# 04_MR_WOLF.net
KiCad netlist of a schematic drawn in Altium Designer
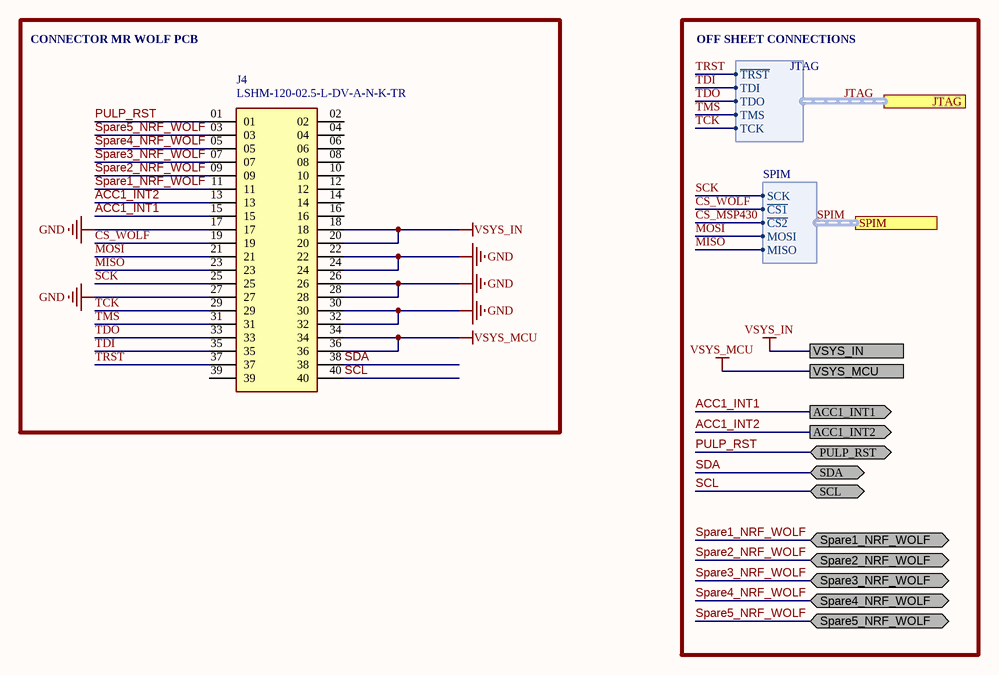
[diagram p0: 04_MR_WOLF.SchDoc]

(export (version "E")
  (design (tool "Eeschema 10.0.6"))
  (components
    (comp (ref "J4")
      (value "LSHM-120-02.5-L-DV-A-N-K-TR")
      (footprint "PcbLib1:SAMTEC_LSHM-120-XX.X-X-DV-A-N-XX")
      (description "Conn Socket and Terminal Strip HDR/SKT 40 POS 0.5mm Solder ST SMD T/R")
      (fields
        (field (name "MANUFACTURER") "Samtec")
        (field (name "MANUFACTURER PART NUMBER") "LSHM-120-02.5-L-DV-A-N-K-TR")
      )
      (libsource (lib "Schlib1") (part "LSHM-120-02.5-L-DV-A-N-K-TR"))
    )
  )
  (nets
    (net (code "3") (name "/ACC1_INT1") (class "Default")
      (node (ref "J4") (pin "15") (pinfunction "15_15") (pintype "passive"))
    )
    (net (code "4") (name "/ACC1_INT2") (class "Default")
      (node (ref "J4") (pin "13") (pinfunction "13_13") (pintype "passive"))
    )
    (net (code "6") (name "/CS_WOLF") (class "Default")
      (node (ref "J4") (pin "19") (pinfunction "19_19") (pintype "passive"))
    )
    (net (code "8") (name "/MISO") (class "Default")
      (node (ref "J4") (pin "23") (pinfunction "23_23") (pintype "passive"))
    )
    (net (code "9") (name "/MOSI") (class "Default")
      (node (ref "J4") (pin "21") (pinfunction "21_21") (pintype "passive"))
    )
    (net (code "10") (name "/PULP_RST") (class "Default")
      (node (ref "J4") (pin "01") (pinfunction "01_01") (pintype "passive"))
    )
    (net (code "11") (name "/SCK") (class "Default")
      (node (ref "J4") (pin "25") (pinfunction "25_25") (pintype "passive"))
    )
    (net (code "12") (name "/SCL") (class "Default")
      (node (ref "J4") (pin "40") (pinfunction "40_40") (pintype "passive"))
    )
    (net (code "13") (name "/SDA") (class "Default")
      (node (ref "J4") (pin "38") (pinfunction "38_38") (pintype "passive"))
    )
    (net (code "15") (name "/Spare1_NRF_WOLF") (class "Default")
      (node (ref "J4") (pin "11") (pinfunction "11_11") (pintype "passive"))
    )
    (net (code "16") (name "/Spare2_NRF_WOLF") (class "Default")
      (node (ref "J4") (pin "09") (pinfunction "09_09") (pintype "passive"))
    )
    (net (code "17") (name "/Spare3_NRF_WOLF") (class "Default")
      (node (ref "J4") (pin "07") (pinfunction "07_07") (pintype "passive"))
    )
    (net (code "18") (name "/Spare4_NRF_WOLF") (class "Default")
      (node (ref "J4") (pin "05") (pinfunction "05_05") (pintype "passive"))
    )
    (net (code "19") (name "/Spare5_NRF_WOLF") (class "Default")
      (node (ref "J4") (pin "03") (pinfunction "03_03") (pintype "passive"))
    )
    (net (code "20") (name "/TCK") (class "Default")
      (node (ref "J4") (pin "29") (pinfunction "29_29") (pintype "passive"))
    )
    (net (code "21") (name "/TDI") (class "Default")
      (node (ref "J4") (pin "35") (pinfunction "35_35") (pintype "passive"))
    )
    (net (code "22") (name "/TDO") (class "Default")
      (node (ref "J4") (pin "33") (pinfunction "33_33") (pintype "passive"))
    )
    (net (code "23") (name "/TMS") (class "Default")
      (node (ref "J4") (pin "31") (pinfunction "31_31") (pintype "passive"))
    )
    (net (code "24") (name "/TRST") (class "Default")
      (node (ref "J4") (pin "37") (pinfunction "37_37") (pintype "passive"))
    )
    (net (code "25") (name "GND") (class "Default")
      (node (ref "J4") (pin "17") (pinfunction "17_17") (pintype "passive"))
      (node (ref "J4") (pin "22") (pinfunction "22_22") (pintype "passive"))
      (node (ref "J4") (pin "24") (pinfunction "24_24") (pintype "passive"))
      (node (ref "J4") (pin "26") (pinfunction "26_26") (pintype "passive"))
      (node (ref "J4") (pin "27") (pinfunction "27_27") (pintype "passive"))
      (node (ref "J4") (pin "28") (pinfunction "28_28") (pintype "passive"))
      (node (ref "J4") (pin "30") (pinfunction "30_30") (pintype "passive"))
      (node (ref "J4") (pin "32") (pinfunction "32_32") (pintype "passive"))
    )
    (net (code "26") (name "VSYS_IN") (class "Default")
      (node (ref "J4") (pin "18") (pinfunction "18_18") (pintype "passive"))
      (node (ref "J4") (pin "20") (pinfunction "20_20") (pintype "passive"))
    )
    (net (code "27") (name "VSYS_MCU") (class "Default")
      (node (ref "J4") (pin "34") (pinfunction "34_34") (pintype "passive"))
      (node (ref "J4") (pin "36") (pinfunction "36_36") (pintype "passive"))
    )
    (net (code "28") (name "unconnected-(J4-Pad02)") (class "Default")
      (node (ref "J4") (pin "02") (pinfunction "02_02") (pintype "passive"))
    )
    (net (code "29") (name "unconnected-(J4-Pad04)") (class "Default")
      (node (ref "J4") (pin "04") (pinfunction "04_04") (pintype "passive"))
    )
    (net (code "30") (name "unconnected-(J4-Pad06)") (class "Default")
      (node (ref "J4") (pin "06") (pinfunction "06_06") (pintype "passive"))
    )
    (net (code "31") (name "unconnected-(J4-Pad08)") (class "Default")
      (node (ref "J4") (pin "08") (pinfunction "08_08") (pintype "passive"))
    )
    (net (code "32") (name "unconnected-(J4-Pad10)") (class "Default")
      (node (ref "J4") (pin "10") (pinfunction "10_10") (pintype "passive"))
    )
    (net (code "33") (name "unconnected-(J4-Pad12)") (class "Default")
      (node (ref "J4") (pin "12") (pinfunction "12_12") (pintype "passive"))
    )
    (net (code "34") (name "unconnected-(J4-Pad14)") (class "Default")
      (node (ref "J4") (pin "14") (pinfunction "14_14") (pintype "passive"))
    )
    (net (code "35") (name "unconnected-(J4-Pad16)") (class "Default")
      (node (ref "J4") (pin "16") (pinfunction "16_16") (pintype "passive"))
    )
    (net (code "36") (name "unconnected-(J4-Pad39)") (class "Default")
      (node (ref "J4") (pin "39") (pinfunction "39_39") (pintype "passive"))
    )
  )
)
